# drivers.net
KiCad netlist of a schematic drawn in Altium Designer
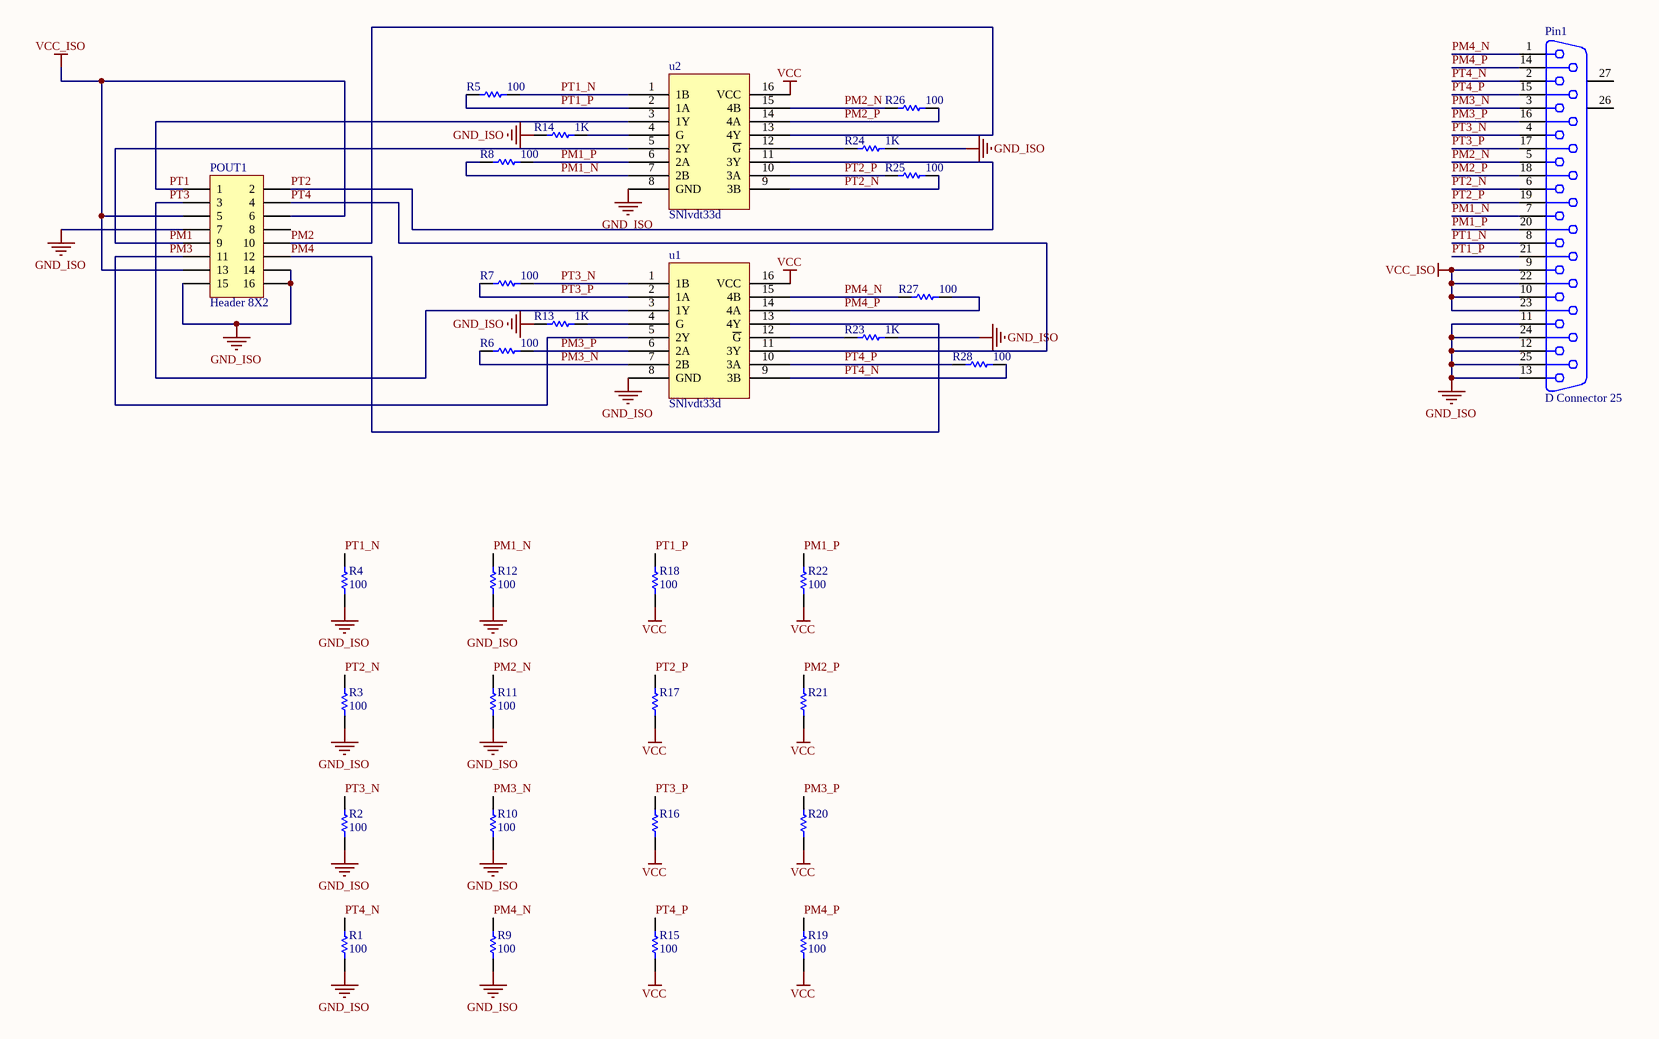
[diagram p0: drivers.SchDoc]

(export (version "E")
  (design (tool "Eeschema 10.0.6"))
  (components
    (comp (ref "Pin1")
      (value "D Connector 25")
      (footprint "DSUB1.385-2H25A")
      (description "Receptacle Assembly, 25 Position, Right Angle")
      (fields (field (name "PUBLISHER") "Altium Limited"))
      (libsource (lib "Miscellaneous Connectors") (part "D Connector 25"))
    )
    (comp (ref "POUT1")
      (value "Header 8X2")
      (footprint "HDR2X8")
      (description "Header, 8-Pin, Dual row")
      (fields (field (name "PUBLISHER") "Altium Limited"))
      (libsource (lib "Miscellaneous Connectors") (part "Header 8X2"))
    )
    (comp (ref "R1")
      (value "100")
      (footprint "2012[0805]")
      (description "Semiconductor Resistor")
      (fields (field (name "Comment") "Res Semi") (field (name "PUBLISHER") "Altium Limited"))
      (libsource (lib "Miscellaneous Devices") (part "Res Semi"))
    )
    (comp (ref "R2")
      (value "100")
      (footprint "2012[0805]")
      (description "Semiconductor Resistor")
      (fields (field (name "Comment") "Res Semi") (field (name "PUBLISHER") "Altium Limited"))
      (libsource (lib "Miscellaneous Devices") (part "Res Semi"))
    )
    (comp (ref "R3")
      (value "100")
      (footprint "2012[0805]")
      (description "Semiconductor Resistor")
      (fields (field (name "Comment") "Res Semi") (field (name "PUBLISHER") "Altium Limited"))
      (libsource (lib "Miscellaneous Devices") (part "Res Semi"))
    )
    (comp (ref "R4")
      (value "100")
      (footprint "2012[0805]")
      (description "Semiconductor Resistor")
      (fields (field (name "Comment") "Res Semi") (field (name "PUBLISHER") "Altium Limited"))
      (libsource (lib "Miscellaneous Devices") (part "Res Semi"))
    )
    (comp (ref "R5")
      (value "100")
      (footprint "2012[0805]")
      (description "Semiconductor Resistor")
      (fields (field (name "Comment") "Res Semi") (field (name "PUBLISHER") "Altium Limited"))
      (libsource (lib "Miscellaneous Devices") (part "Res Semi"))
    )
    (comp (ref "R6")
      (value "100")
      (footprint "2012[0805]")
      (description "Semiconductor Resistor")
      (fields (field (name "Comment") "Res Semi") (field (name "PUBLISHER") "Altium Limited"))
      (libsource (lib "Miscellaneous Devices") (part "Res Semi"))
    )
    (comp (ref "R7")
      (value "100")
      (footprint "2012[0805]")
      (description "Semiconductor Resistor")
      (fields (field (name "Comment") "Res Semi") (field (name "PUBLISHER") "Altium Limited"))
      (libsource (lib "Miscellaneous Devices") (part "Res Semi"))
    )
    (comp (ref "R8")
      (value "100")
      (footprint "2012[0805]")
      (description "Semiconductor Resistor")
      (fields (field (name "Comment") "Res Semi") (field (name "PUBLISHER") "Altium Limited"))
      (libsource (lib "Miscellaneous Devices") (part "Res Semi"))
    )
    (comp (ref "R9")
      (value "100")
      (footprint "2012[0805]")
      (description "Semiconductor Resistor")
      (fields (field (name "Comment") "Res Semi") (field (name "PUBLISHER") "Altium Limited"))
      (libsource (lib "Miscellaneous Devices") (part "Res Semi"))
    )
    (comp (ref "R10")
      (value "100")
      (footprint "2012[0805]")
      (description "Semiconductor Resistor")
      (fields (field (name "Comment") "Res Semi") (field (name "PUBLISHER") "Altium Limited"))
      (libsource (lib "Miscellaneous Devices") (part "Res Semi"))
    )
    (comp (ref "R11")
      (value "100")
      (footprint "2012[0805]")
      (description "Semiconductor Resistor")
      (fields (field (name "Comment") "Res Semi") (field (name "PUBLISHER") "Altium Limited"))
      (libsource (lib "Miscellaneous Devices") (part "Res Semi"))
    )
    (comp (ref "R12")
      (value "100")
      (footprint "2012[0805]")
      (description "Semiconductor Resistor")
      (fields (field (name "Comment") "Res Semi") (field (name "PUBLISHER") "Altium Limited"))
      (libsource (lib "Miscellaneous Devices") (part "Res Semi"))
    )
    (comp (ref "R13")
      (value "1K")
      (footprint "2012[0805]")
      (description "Semiconductor Resistor")
      (fields (field (name "Comment") "Res Semi") (field (name "PUBLISHER") "Altium Limited"))
      (libsource (lib "Miscellaneous Devices") (part "Res Semi"))
    )
    (comp (ref "R14")
      (value "1K")
      (footprint "2012[0805]")
      (description "Semiconductor Resistor")
      (fields (field (name "Comment") "Res Semi") (field (name "PUBLISHER") "Altium Limited"))
      (libsource (lib "Miscellaneous Devices") (part "Res Semi"))
    )
    (comp (ref "R15")
      (value "100")
      (footprint "2012[0805]")
      (description "Semiconductor Resistor")
      (fields (field (name "Comment") "Res Semi") (field (name "PUBLISHER") "Altium Limited"))
      (libsource (lib "Miscellaneous Devices") (part "Res Semi"))
    )
    (comp (ref "R16")
      (value "Res Semi")
      (footprint "2012[0805]")
      (description "Semiconductor Resistor")
      (fields (field (name "PUBLISHER") "Altium Limited"))
      (libsource (lib "Miscellaneous Devices") (part "Res Semi"))
    )
    (comp (ref "R17")
      (value "Res Semi")
      (footprint "2012[0805]")
      (description "Semiconductor Resistor")
      (fields (field (name "PUBLISHER") "Altium Limited"))
      (libsource (lib "Miscellaneous Devices") (part "Res Semi"))
    )
    (comp (ref "R18")
      (value "100")
      (footprint "2012[0805]")
      (description "Semiconductor Resistor")
      (fields (field (name "Comment") "Res Semi") (field (name "PUBLISHER") "Altium Limited"))
      (libsource (lib "Miscellaneous Devices") (part "Res Semi"))
    )
    (comp (ref "R19")
      (value "100")
      (footprint "2012[0805]")
      (description "Semiconductor Resistor")
      (fields (field (name "Comment") "Res Semi") (field (name "PUBLISHER") "Altium Limited"))
      (libsource (lib "Miscellaneous Devices") (part "Res Semi"))
    )
    (comp (ref "R20")
      (value "Res Semi")
      (footprint "2012[0805]")
      (description "Semiconductor Resistor")
      (fields (field (name "PUBLISHER") "Altium Limited"))
      (libsource (lib "Miscellaneous Devices") (part "Res Semi"))
    )
    (comp (ref "R21")
      (value "Res Semi")
      (footprint "2012[0805]")
      (description "Semiconductor Resistor")
      (fields (field (name "PUBLISHER") "Altium Limited"))
      (libsource (lib "Miscellaneous Devices") (part "Res Semi"))
    )
    (comp (ref "R22")
      (value "100")
      (footprint "2012[0805]")
      (description "Semiconductor Resistor")
      (fields (field (name "Comment") "Res Semi") (field (name "PUBLISHER") "Altium Limited"))
      (libsource (lib "Miscellaneous Devices") (part "Res Semi"))
    )
    (comp (ref "R23")
      (value "1K")
      (footprint "2012[0805]")
      (description "Semiconductor Resistor")
      (fields (field (name "Comment") "Res Semi") (field (name "PUBLISHER") "Altium Limited"))
      (libsource (lib "Miscellaneous Devices") (part "Res Semi"))
    )
    (comp (ref "R24")
      (value "1K")
      (footprint "2012[0805]")
      (description "Semiconductor Resistor")
      (fields (field (name "Comment") "Res Semi") (field (name "PUBLISHER") "Altium Limited"))
      (libsource (lib "Miscellaneous Devices") (part "Res Semi"))
    )
    (comp (ref "R25")
      (value "100")
      (footprint "2012[0805]")
      (description "Semiconductor Resistor")
      (fields (field (name "Comment") "Res Semi") (field (name "PUBLISHER") "Altium Limited"))
      (libsource (lib "Miscellaneous Devices") (part "Res Semi"))
    )
    (comp (ref "R26")
      (value "100")
      (footprint "2012[0805]")
      (description "Semiconductor Resistor")
      (fields (field (name "Comment") "Res Semi") (field (name "PUBLISHER") "Altium Limited"))
      (libsource (lib "Miscellaneous Devices") (part "Res Semi"))
    )
    (comp (ref "R27")
      (value "100")
      (footprint "2012[0805]")
      (description "Semiconductor Resistor")
      (fields (field (name "Comment") "Res Semi") (field (name "PUBLISHER") "Altium Limited"))
      (libsource (lib "Miscellaneous Devices") (part "Res Semi"))
    )
    (comp (ref "R28")
      (value "100")
      (footprint "2012[0805]")
      (description "Semiconductor Resistor")
      (fields (field (name "Comment") "Res Semi") (field (name "PUBLISHER") "Altium Limited"))
      (libsource (lib "Miscellaneous Devices") (part "Res Semi"))
    )
    (comp (ref "u1")
      (value "SNlvdt33d")
      (footprint "R-16")
      (libsource (lib "miscomponentes") (part "SNlvdt33d"))
    )
    (comp (ref "u2")
      (value "SNlvdt33d")
      (footprint "R-16")
      (libsource (lib "miscomponentes") (part "SNlvdt33d"))
    )
  )
  (nets
    (net (code "1") (name "/PM1") (class "Default")
      (node (ref "POUT1") (pin "9") (pinfunction "9_9") (pintype "passive"))
      (node (ref "u2") (pin "5") (pinfunction "2Y_5") (pintype "passive"))
    )
    (net (code "2") (name "/PM1_N") (class "Default")
      (node (ref "Pin1") (pin "7") (pinfunction "7_7") (pintype "passive"))
      (node (ref "R12") (pin "1") (pinfunction "1_1") (pintype "passive"))
      (node (ref "R8") (pin "1") (pinfunction "1_1") (pintype "passive"))
      (node (ref "u2") (pin "7") (pinfunction "2B_7") (pintype "passive"))
    )
    (net (code "3") (name "/PM1_P") (class "Default")
      (node (ref "Pin1") (pin "20") (pinfunction "20_20") (pintype "passive"))
      (node (ref "R22") (pin "1") (pinfunction "1_1") (pintype "passive"))
      (node (ref "R8") (pin "2") (pinfunction "2_2") (pintype "passive"))
      (node (ref "u2") (pin "6") (pinfunction "2A_6") (pintype "passive"))
    )
    (net (code "4") (name "/PM2") (class "Default")
      (node (ref "POUT1") (pin "10") (pinfunction "10_10") (pintype "passive"))
      (node (ref "u2") (pin "13") (pinfunction "4Y_13") (pintype "passive"))
    )
    (net (code "5") (name "/PM2_N") (class "Default")
      (node (ref "Pin1") (pin "5") (pinfunction "5_5") (pintype "passive"))
      (node (ref "R11") (pin "1") (pinfunction "1_1") (pintype "passive"))
      (node (ref "R26") (pin "1") (pinfunction "1_1") (pintype "passive"))
      (node (ref "u2") (pin "15") (pinfunction "4B_15") (pintype "passive"))
    )
    (net (code "6") (name "/PM2_P") (class "Default")
      (node (ref "Pin1") (pin "18") (pinfunction "18_18") (pintype "passive"))
      (node (ref "R21") (pin "1") (pinfunction "1_1") (pintype "passive"))
      (node (ref "R26") (pin "2") (pinfunction "2_2") (pintype "passive"))
      (node (ref "u2") (pin "14") (pinfunction "4A_14") (pintype "passive"))
    )
    (net (code "7") (name "/PM3") (class "Default")
      (node (ref "POUT1") (pin "11") (pinfunction "11_11") (pintype "passive"))
      (node (ref "u1") (pin "5") (pinfunction "2Y_5") (pintype "passive"))
    )
    (net (code "8") (name "/PM3_N") (class "Default")
      (node (ref "Pin1") (pin "3") (pinfunction "3_3") (pintype "passive"))
      (node (ref "R10") (pin "1") (pinfunction "1_1") (pintype "passive"))
      (node (ref "R6") (pin "1") (pinfunction "1_1") (pintype "passive"))
      (node (ref "u1") (pin "7") (pinfunction "2B_7") (pintype "passive"))
    )
    (net (code "9") (name "/PM3_P") (class "Default")
      (node (ref "Pin1") (pin "16") (pinfunction "16_16") (pintype "passive"))
      (node (ref "R20") (pin "1") (pinfunction "1_1") (pintype "passive"))
      (node (ref "R6") (pin "2") (pinfunction "2_2") (pintype "passive"))
      (node (ref "u1") (pin "6") (pinfunction "2A_6") (pintype "passive"))
    )
    (net (code "10") (name "/PM4") (class "Default")
      (node (ref "POUT1") (pin "12") (pinfunction "12_12") (pintype "passive"))
      (node (ref "u1") (pin "13") (pinfunction "4Y_13") (pintype "passive"))
    )
    (net (code "11") (name "/PM4_N") (class "Default")
      (node (ref "Pin1") (pin "1") (pinfunction "1_1") (pintype "passive"))
      (node (ref "R27") (pin "1") (pinfunction "1_1") (pintype "passive"))
      (node (ref "R9") (pin "1") (pinfunction "1_1") (pintype "passive"))
      (node (ref "u1") (pin "15") (pinfunction "4B_15") (pintype "passive"))
    )
    (net (code "12") (name "/PM4_P") (class "Default")
      (node (ref "Pin1") (pin "14") (pinfunction "14_14") (pintype "passive"))
      (node (ref "R19") (pin "1") (pinfunction "1_1") (pintype "passive"))
      (node (ref "R27") (pin "2") (pinfunction "2_2") (pintype "passive"))
      (node (ref "u1") (pin "14") (pinfunction "4A_14") (pintype "passive"))
    )
    (net (code "13") (name "/PT1") (class "Default")
      (node (ref "POUT1") (pin "1") (pinfunction "1_1") (pintype "passive"))
      (node (ref "u2") (pin "3") (pinfunction "1Y_3") (pintype "passive"))
    )
    (net (code "14") (name "/PT1_N") (class "Default")
      (node (ref "Pin1") (pin "8") (pinfunction "8_8") (pintype "passive"))
      (node (ref "R4") (pin "1") (pinfunction "1_1") (pintype "passive"))
      (node (ref "R5") (pin "2") (pinfunction "2_2") (pintype "passive"))
      (node (ref "u2") (pin "1") (pinfunction "1B_1") (pintype "passive"))
    )
    (net (code "15") (name "/PT1_P") (class "Default")
      (node (ref "Pin1") (pin "21") (pinfunction "21_21") (pintype "passive"))
      (node (ref "R18") (pin "1") (pinfunction "1_1") (pintype "passive"))
      (node (ref "R5") (pin "1") (pinfunction "1_1") (pintype "passive"))
      (node (ref "u2") (pin "2") (pinfunction "1A_2") (pintype "passive"))
    )
    (net (code "16") (name "/PT2") (class "Default")
      (node (ref "POUT1") (pin "2") (pinfunction "2_2") (pintype "passive"))
      (node (ref "u2") (pin "11") (pinfunction "3Y_11") (pintype "passive"))
    )
    (net (code "17") (name "/PT2_N") (class "Default")
      (node (ref "Pin1") (pin "6") (pinfunction "6_6") (pintype "passive"))
      (node (ref "R25") (pin "2") (pinfunction "2_2") (pintype "passive"))
      (node (ref "R3") (pin "1") (pinfunction "1_1") (pintype "passive"))
      (node (ref "u2") (pin "9") (pinfunction "3B_9") (pintype "passive"))
    )
    (net (code "18") (name "/PT2_P") (class "Default")
      (node (ref "Pin1") (pin "19") (pinfunction "19_19") (pintype "passive"))
      (node (ref "R17") (pin "1") (pinfunction "1_1") (pintype "passive"))
      (node (ref "R25") (pin "1") (pinfunction "1_1") (pintype "passive"))
      (node (ref "u2") (pin "10") (pinfunction "3A_10") (pintype "passive"))
    )
    (net (code "19") (name "/PT3") (class "Default")
      (node (ref "POUT1") (pin "3") (pinfunction "3_3") (pintype "passive"))
      (node (ref "u1") (pin "3") (pinfunction "1Y_3") (pintype "passive"))
    )
    (net (code "20") (name "/PT3_N") (class "Default")
      (node (ref "Pin1") (pin "4") (pinfunction "4_4") (pintype "passive"))
      (node (ref "R2") (pin "1") (pinfunction "1_1") (pintype "passive"))
      (node (ref "R7") (pin "2") (pinfunction "2_2") (pintype "passive"))
      (node (ref "u1") (pin "1") (pinfunction "1B_1") (pintype "passive"))
    )
    (net (code "21") (name "/PT3_P") (class "Default")
      (node (ref "Pin1") (pin "17") (pinfunction "17_17") (pintype "passive"))
      (node (ref "R16") (pin "1") (pinfunction "1_1") (pintype "passive"))
      (node (ref "R7") (pin "1") (pinfunction "1_1") (pintype "passive"))
      (node (ref "u1") (pin "2") (pinfunction "1A_2") (pintype "passive"))
    )
    (net (code "22") (name "/PT4") (class "Default")
      (node (ref "POUT1") (pin "4") (pinfunction "4_4") (pintype "passive"))
      (node (ref "u1") (pin "11") (pinfunction "3Y_11") (pintype "passive"))
    )
    (net (code "23") (name "/PT4_N") (class "Default")
      (node (ref "Pin1") (pin "2") (pinfunction "2_2") (pintype "passive"))
      (node (ref "R1") (pin "1") (pinfunction "1_1") (pintype "passive"))
      (node (ref "R28") (pin "2") (pinfunction "2_2") (pintype "passive"))
      (node (ref "u1") (pin "9") (pinfunction "3B_9") (pintype "passive"))
    )
    (net (code "24") (name "/PT4_P") (class "Default")
      (node (ref "Pin1") (pin "15") (pinfunction "15_15") (pintype "passive"))
      (node (ref "R15") (pin "1") (pinfunction "1_1") (pintype "passive"))
      (node (ref "R28") (pin "1") (pinfunction "1_1") (pintype "passive"))
      (node (ref "u1") (pin "10") (pinfunction "3A_10") (pintype "passive"))
    )
    (net (code "25") (name "GND_ISO") (class "Default")
      (node (ref "POUT1") (pin "14") (pinfunction "14_14") (pintype "passive"))
      (node (ref "POUT1") (pin "15") (pinfunction "15_15") (pintype "passive"))
      (node (ref "POUT1") (pin "16") (pinfunction "16_16") (pintype "passive"))
      (node (ref "POUT1") (pin "7") (pinfunction "7_7") (pintype "passive"))
      (node (ref "Pin1") (pin "11") (pinfunction "11_11") (pintype "passive"))
      (node (ref "Pin1") (pin "12") (pinfunction "12_12") (pintype "passive"))
      (node (ref "Pin1") (pin "13") (pinfunction "13_13") (pintype "passive"))
      (node (ref "Pin1") (pin "24") (pinfunction "24_24") (pintype "passive"))
      (node (ref "Pin1") (pin "25") (pinfunction "25_25") (pintype "passive"))
      (node (ref "R1") (pin "2") (pinfunction "2_2") (pintype "passive"))
      (node (ref "R10") (pin "2") (pinfunction "2_2") (pintype "passive"))
      (node (ref "R11") (pin "2") (pinfunction "2_2") (pintype "passive"))
      (node (ref "R12") (pin "2") (pinfunction "2_2") (pintype "passive"))
      (node (ref "R13") (pin "1") (pinfunction "1_1") (pintype "passive"))
      (node (ref "R14") (pin "1") (pinfunction "1_1") (pintype "passive"))
      (node (ref "R2") (pin "2") (pinfunction "2_2") (pintype "passive"))
      (node (ref "R23") (pin "2") (pinfunction "2_2") (pintype "passive"))
      (node (ref "R24") (pin "2") (pinfunction "2_2") (pintype "passive"))
      (node (ref "R3") (pin "2") (pinfunction "2_2") (pintype "passive"))
      (node (ref "R4") (pin "2") (pinfunction "2_2") (pintype "passive"))
      (node (ref "R9") (pin "2") (pinfunction "2_2") (pintype "passive"))
      (node (ref "u1") (pin "8") (pinfunction "GND_8") (pintype "passive"))
      (node (ref "u2") (pin "8") (pinfunction "GND_8") (pintype "passive"))
    )
    (net (code "26") (name "Net-(u1-G)") (class "Default")
      (node (ref "R13") (pin "2") (pinfunction "2_2") (pintype "passive"))
      (node (ref "u1") (pin "4") (pinfunction "G_4") (pintype "passive"))
    )
    (net (code "27") (name "Net-(u1-~{G})") (class "Default")
      (node (ref "R23") (pin "1") (pinfunction "1_1") (pintype "passive"))
      (node (ref "u1") (pin "12") (pinfunction "~{G}_12") (pintype "passive"))
    )
    (net (code "28") (name "Net-(u2-G)") (class "Default")
      (node (ref "R14") (pin "2") (pinfunction "2_2") (pintype "passive"))
      (node (ref "u2") (pin "4") (pinfunction "G_4") (pintype "passive"))
    )
    (net (code "29") (name "Net-(u2-~{G})") (class "Default")
      (node (ref "R24") (pin "1") (pinfunction "1_1") (pintype "passive"))
      (node (ref "u2") (pin "12") (pinfunction "~{G}_12") (pintype "passive"))
    )
    (net (code "30") (name "VCC") (class "Default")
      (node (ref "R15") (pin "2") (pinfunction "2_2") (pintype "passive"))
      (node (ref "R16") (pin "2") (pinfunction "2_2") (pintype "passive"))
      (node (ref "R17") (pin "2") (pinfunction "2_2") (pintype "passive"))
      (node (ref "R18") (pin "2") (pinfunction "2_2") (pintype "passive"))
      (node (ref "R19") (pin "2") (pinfunction "2_2") (pintype "passive"))
      (node (ref "R20") (pin "2") (pinfunction "2_2") (pintype "passive"))
      (node (ref "R21") (pin "2") (pinfunction "2_2") (pintype "passive"))
      (node (ref "R22") (pin "2") (pinfunction "2_2") (pintype "passive"))
      (node (ref "u1") (pin "16") (pinfunction "VCC_16") (pintype "passive"))
      (node (ref "u2") (pin "16") (pinfunction "VCC_16") (pintype "passive"))
    )
    (net (code "31") (name "VCC_ISO") (class "Default")
      (node (ref "POUT1") (pin "13") (pinfunction "13_13") (pintype "passive"))
      (node (ref "POUT1") (pin "5") (pinfunction "5_5") (pintype "passive"))
      (node (ref "POUT1") (pin "6") (pinfunction "6_6") (pintype "passive"))
      (node (ref "Pin1") (pin "10") (pinfunction "10_10") (pintype "passive"))
      (node (ref "Pin1") (pin "22") (pinfunction "22_22") (pintype "passive"))
      (node (ref "Pin1") (pin "23") (pinfunction "23_23") (pintype "passive"))
      (node (ref "Pin1") (pin "9") (pinfunction "9_9") (pintype "passive"))
    )
    (net (code "32") (name "unconnected-(POUT1-Pad8)") (class "Default")
      (node (ref "POUT1") (pin "8") (pinfunction "8_8") (pintype "passive"))
    )
    (net (code "33") (name "unconnected-(Pin1-MH1-Pad26)") (class "Default")
      (node (ref "Pin1") (pin "26") (pinfunction "MH1_26") (pintype "passive"))
    )
    (net (code "34") (name "unconnected-(Pin1-MH2-Pad27)") (class "Default")
      (node (ref "Pin1") (pin "27") (pinfunction "MH2_27") (pintype "passive"))
    )
  )
)
